# Sensor.net
KiCad netlist of a schematic drawn in Altium Designer
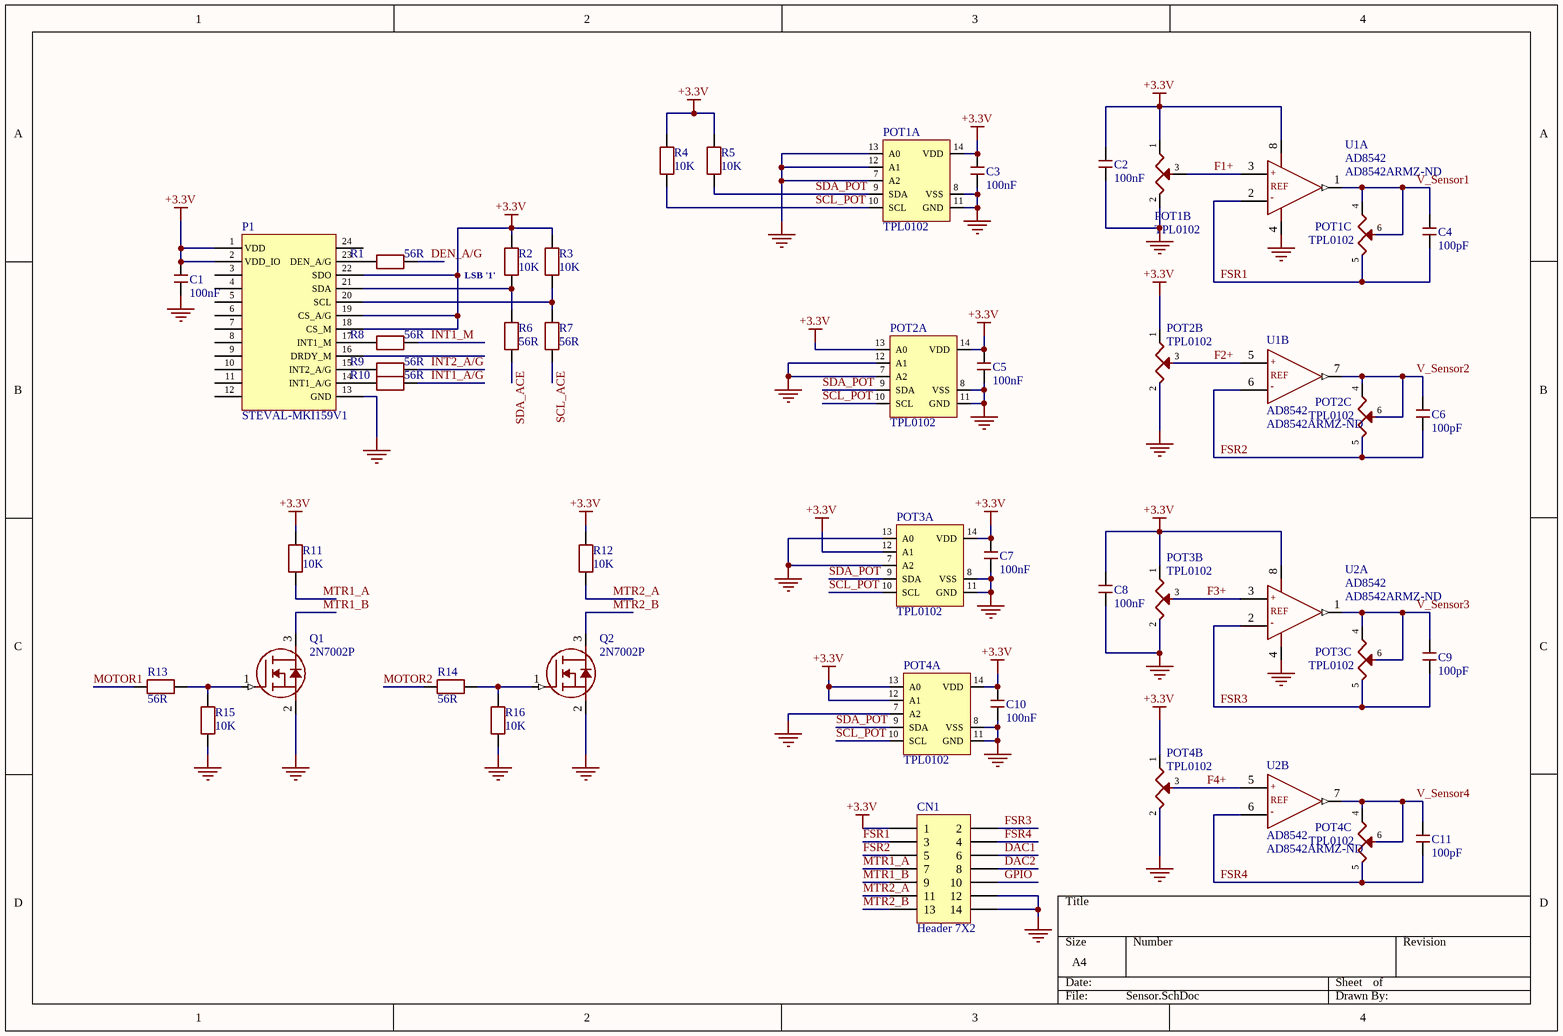
[diagram p0: Sensor.SchDoc]

(export (version "E")
  (design (tool "Eeschema 10.0.6"))
  (components
    (comp (ref "C1")
      (value "100nF")
      (footprint "CAP0805[2012]MD-BO")
      (description "CERAMIC SMD 0805 100nF 50V 10% X7R")
      (libsource (lib "Estimulador") (part "SMD 0805 100nF 50V 10% X7R"))
    )
    (comp (ref "C2")
      (value "100nF")
      (footprint "CAP0805[2012]MD-BO")
      (description "CERAMIC SMD 0805 100nF 50V 10% X7R")
      (libsource (lib "Estimulador") (part "SMD 0805 100nF 50V 10% X7R"))
    )
    (comp (ref "C3")
      (value "100nF")
      (footprint "CAP0805[2012]MD-BO")
      (description "CERAMIC SMD 0805 100nF 50V 10% X7R")
      (libsource (lib "Estimulador") (part "SMD 0805 100nF 50V 10% X7R"))
    )
    (comp (ref "C4")
      (value "100pF")
      (footprint "CAP0805[2012]MD-BO")
      (description "CERAMIC SMD 0805 100pF 50V 5% C0G")
      (libsource (lib "Estimulador") (part "SMD 0805 100pF 50V 5% C0G"))
    )
    (comp (ref "C5")
      (value "100nF")
      (footprint "CAP0805[2012]MD-BO")
      (description "CERAMIC SMD 0805 100nF 50V 10% X7R")
      (libsource (lib "Estimulador") (part "SMD 0805 100nF 50V 10% X7R"))
    )
    (comp (ref "C6")
      (value "100pF")
      (footprint "CAP0805[2012]MD-BO")
      (description "CERAMIC SMD 0805 100pF 50V 5% C0G")
      (libsource (lib "Estimulador") (part "SMD 0805 100pF 50V 5% C0G"))
    )
    (comp (ref "C7")
      (value "100nF")
      (footprint "CAP0805[2012]MD-BO")
      (description "CERAMIC SMD 0805 100nF 50V 10% X7R")
      (libsource (lib "Estimulador") (part "SMD 0805 100nF 50V 10% X7R"))
    )
    (comp (ref "C8")
      (value "100nF")
      (footprint "CAP0805[2012]MD-BO")
      (description "CERAMIC SMD 0805 100nF 50V 10% X7R")
      (libsource (lib "Estimulador") (part "SMD 0805 100nF 50V 10% X7R"))
    )
    (comp (ref "C9")
      (value "100pF")
      (footprint "CAP0805[2012]MD-BO")
      (description "CERAMIC SMD 0805 100pF 50V 5% C0G")
      (libsource (lib "Estimulador") (part "SMD 0805 100pF 50V 5% C0G"))
    )
    (comp (ref "C10")
      (value "100nF")
      (footprint "CAP0805[2012]MD-BO")
      (description "CERAMIC SMD 0805 100nF 50V 10% X7R")
      (libsource (lib "Estimulador") (part "SMD 0805 100nF 50V 10% X7R"))
    )
    (comp (ref "C11")
      (value "100pF")
      (footprint "CAP0805[2012]MD-BO")
      (description "CERAMIC SMD 0805 100pF 50V 5% C0G")
      (libsource (lib "Estimulador") (part "SMD 0805 100pF 50V 5% C0G"))
    )
    (comp (ref "CN1")
      (value "Header 7X2")
      (footprint "HDR2X7")
      (description "Header, 7-Pin, Dual row")
      (fields (field (name "PUBLISHER") "Altium Limited"))
      (libsource (lib "Miscellaneous Connectors") (part "Header 7X2"))
    )
    (comp (ref "P1")
      (value "STEVAL-MKI159V1")
      (footprint "STEVAL-MKI159V1 (2)")
      (description "STEVAL-MKI159V1 MEMS")
      (libsource (lib "MastersSystem") (part "STEVAL-MKI159V1"))
    )
    (comp (ref "POT1")
      (value "TPL0102")
      (footprint "TPL0102")
      (libsource (lib "MastersSystem2") (part "TPL0102"))
    )
    (comp (ref "POT2") (value "TPL0102") (footprint "TPL0102") (libsource (lib "") (part "TPL0102_1")))
    (comp (ref "POT3") (value "TPL0102") (footprint "TPL0102") (libsource (lib "") (part "TPL0102_1")))
    (comp (ref "POT4")
      (value "TPL0102")
      (footprint "TPL0102")
      (libsource (lib "MastersSystem2") (part "TPL0102"))
    )
    (comp (ref "Q1")
      (value "2N7002P")
      (footprint "SOT23-3")
      (description "MOSFET N-CH 60V 360mA SOT23-3")
      (libsource (lib "Transistors") (part "2N7002P,215"))
    )
    (comp (ref "Q2")
      (value "2N7002P")
      (footprint "SOT23-3")
      (description "MOSFET N-CH 60V 360mA SOT23-3")
      (libsource (lib "Transistors") (part "2N7002P,215"))
    )
    (comp (ref "R1")
      (value "56R")
      (footprint "RES0805[2012]MD-BO")
      (description "RESISTOR SMD 0805 56R 5% 0.125W")
      (libsource (lib "") (part "SMD 0805 56R 5% 0.125W_1"))
    )
    (comp (ref "R2")
      (value "10K")
      (footprint "RES0805[2012]MD")
      (description "RESISTOR SMD 0805 10K 5% 0.125W")
      (libsource (lib "Estimulador") (part "SMD 0805 10K 5% 0.125W"))
    )
    (comp (ref "R3")
      (value "10K")
      (footprint "RES0805[2012]MD")
      (description "RESISTOR SMD 0805 10K 5% 0.125W")
      (libsource (lib "Estimulador") (part "SMD 0805 10K 5% 0.125W"))
    )
    (comp (ref "R4")
      (value "10K")
      (footprint "RES0805[2012]MD")
      (description "RESISTOR SMD 0805 10K 5% 0.125W")
      (libsource (lib "Estimulador") (part "SMD 0805 10K 5% 0.125W"))
    )
    (comp (ref "R5")
      (value "10K")
      (footprint "RES0805[2012]MD")
      (description "RESISTOR SMD 0805 10K 5% 0.125W")
      (libsource (lib "Estimulador") (part "SMD 0805 10K 5% 0.125W"))
    )
    (comp (ref "R6")
      (value "56R")
      (footprint "RES0805[2012]MD-BO")
      (description "RESISTOR SMD 0805 56R 5% 0.125W")
      (libsource (lib "Resistors") (part "SMD 0805 56R 5% 0.125W"))
    )
    (comp (ref "R7")
      (value "56R")
      (footprint "RES0805[2012]MD-BO")
      (description "RESISTOR SMD 0805 56R 5% 0.125W")
      (libsource (lib "Resistors") (part "SMD 0805 56R 5% 0.125W"))
    )
    (comp (ref "R8")
      (value "56R")
      (footprint "RES0805[2012]MD-BO")
      (description "RESISTOR SMD 0805 56R 5% 0.125W")
      (libsource (lib "") (part "SMD 0805 56R 5% 0.125W_1"))
    )
    (comp (ref "R9")
      (value "56R")
      (footprint "RES0805[2012]MD-BO")
      (description "RESISTOR SMD 0805 56R 5% 0.125W")
      (libsource (lib "") (part "SMD 0805 56R 5% 0.125W_1"))
    )
    (comp (ref "R10")
      (value "56R")
      (footprint "RES0805[2012]MD-BO")
      (description "RESISTOR SMD 0805 56R 5% 0.125W")
      (libsource (lib "") (part "SMD 0805 56R 5% 0.125W_1"))
    )
    (comp (ref "R11")
      (value "10K")
      (footprint "RES0805[2012]MD-BO")
      (description "RESISTOR SMD 0805 10K 5% 0.125W")
      (libsource (lib "Estimulador") (part "SMD 0805 10K 5% 0.125W"))
    )
    (comp (ref "R12")
      (value "10K")
      (footprint "RES0805[2012]MD-BO")
      (description "RESISTOR SMD 0805 10K 5% 0.125W")
      (libsource (lib "Estimulador") (part "SMD 0805 10K 5% 0.125W"))
    )
    (comp (ref "R13")
      (value "56R")
      (footprint "RES0805[2012]MD-BO")
      (description "RESISTOR SMD 0805 56R 5% 0.125W")
      (libsource (lib "Estimulador") (part "SMD 0805 56R 5% 0.125W"))
    )
    (comp (ref "R14")
      (value "56R")
      (footprint "RES0805[2012]MD-BO")
      (description "RESISTOR SMD 0805 56R 5% 0.125W")
      (libsource (lib "Estimulador") (part "SMD 0805 56R 5% 0.125W"))
    )
    (comp (ref "R15")
      (value "10K")
      (footprint "RES0805[2012]MD-BO")
      (description "RESISTOR SMD 0805 10K 5% 0.125W")
      (libsource (lib "Estimulador") (part "SMD 0805 10K 5% 0.125W"))
    )
    (comp (ref "R16")
      (value "10K")
      (footprint "RES0805[2012]MD-BO")
      (description "RESISTOR SMD 0805 10K 5% 0.125W")
      (libsource (lib "Estimulador") (part "SMD 0805 10K 5% 0.125W"))
    )
    (comp (ref "U1")
      (value "AD8542")
      (footprint "MSOP8")
      (fields (field (name "SUPPLIER PART NUMBER 1") "AD8542ARMZ-ND"))
      (libsource (lib "MastersSystem") (part "AD8542"))
    )
    (comp (ref "U2")
      (value "AD8542")
      (footprint "MSOP8")
      (fields (field (name "SUPPLIER PART NUMBER 1") "AD8542ARMZ-ND"))
      (libsource (lib "MastersSystem") (part "AD8542"))
    )
  )
  (nets
    (net (code "1") (name "+3.3V") (class "Default")
      (node (ref "C1") (pin "1") (pinfunction "1_1") (pintype "passive"))
      (node (ref "C10") (pin "1") (pinfunction "1_1") (pintype "passive"))
      (node (ref "C2") (pin "1") (pinfunction "1_1") (pintype "passive"))
      (node (ref "C3") (pin "1") (pinfunction "1_1") (pintype "passive"))
      (node (ref "C5") (pin "1") (pinfunction "1_1") (pintype "passive"))
      (node (ref "C7") (pin "1") (pinfunction "1_1") (pintype "passive"))
      (node (ref "C8") (pin "1") (pinfunction "1_1") (pintype "passive"))
      (node (ref "CN1") (pin "1") (pinfunction "1_1") (pintype "passive"))
      (node (ref "P1") (pin "1") (pinfunction "VDD_1") (pintype "passive"))
      (node (ref "P1") (pin "18") (pinfunction "CS_M_18") (pintype "passive"))
      (node (ref "P1") (pin "19") (pinfunction "CS_A/G_19") (pintype "passive"))
      (node (ref "P1") (pin "2") (pinfunction "VDD_IO_2") (pintype "passive"))
      (node (ref "P1") (pin "22") (pinfunction "SDO_22") (pintype "passive"))
      (node (ref "POT1") (pin "1") (pinfunction "HA_1") (pintype "passive"))
      (node (ref "POT1") (pin "14") (pinfunction "VDD_14") (pintype "passive"))
      (node (ref "POT2") (pin "1") (pinfunction "HA_1") (pintype "passive"))
      (node (ref "POT2") (pin "13") (pinfunction "A0_13") (pintype "passive"))
      (node (ref "POT2") (pin "14") (pinfunction "VDD_14") (pintype "passive"))
      (node (ref "POT3") (pin "1") (pinfunction "HA_1") (pintype "passive"))
      (node (ref "POT3") (pin "12") (pinfunction "A1_12") (pintype "passive"))
      (node (ref "POT3") (pin "14") (pinfunction "VDD_14") (pintype "passive"))
      (node (ref "POT4") (pin "1") (pinfunction "HA_1") (pintype "passive"))
      (node (ref "POT4") (pin "12") (pinfunction "A1_12") (pintype "passive"))
      (node (ref "POT4") (pin "13") (pinfunction "A0_13") (pintype "passive"))
      (node (ref "POT4") (pin "14") (pinfunction "VDD_14") (pintype "passive"))
      (node (ref "R11") (pin "2") (pinfunction "2_2") (pintype "passive"))
      (node (ref "R12") (pin "2") (pinfunction "2_2") (pintype "passive"))
      (node (ref "R2") (pin "2") (pinfunction "2_2") (pintype "passive"))
      (node (ref "R3") (pin "2") (pinfunction "2_2") (pintype "passive"))
      (node (ref "R4") (pin "2") (pinfunction "2_2") (pintype "passive"))
      (node (ref "R5") (pin "2") (pinfunction "2_2") (pintype "passive"))
      (node (ref "U1") (pin "8") (pinfunction "V+_8") (pintype "power_in"))
      (node (ref "U2") (pin "8") (pinfunction "V+_8") (pintype "power_in"))
    )
    (net (code "2") (name "/DAC1") (class "Default")
      (node (ref "CN1") (pin "6") (pinfunction "6_6") (pintype "passive"))
    )
    (net (code "3") (name "/DAC2") (class "Default")
      (node (ref "CN1") (pin "8") (pinfunction "8_8") (pintype "passive"))
    )
    (net (code "4") (name "/DEN_A{slash}G") (class "Default")
      (node (ref "R1") (pin "1") (pinfunction "1_1") (pintype "passive"))
    )
    (net (code "5") (name "/F1+") (class "Default")
      (node (ref "POT1") (pin "3") (pinfunction "WA_3") (pintype "passive"))
      (node (ref "U1") (pin "3") (pinfunction "+IN_A_3") (pintype "passive"))
    )
    (net (code "6") (name "/F2+") (class "Default")
      (node (ref "POT2") (pin "3") (pinfunction "WA_3") (pintype "passive"))
      (node (ref "U1") (pin "5") (pinfunction "+IN_B_5") (pintype "passive"))
    )
    (net (code "7") (name "/F3+") (class "Default")
      (node (ref "POT3") (pin "3") (pinfunction "WA_3") (pintype "passive"))
      (node (ref "U2") (pin "3") (pinfunction "+IN_A_3") (pintype "passive"))
    )
    (net (code "8") (name "/F4+") (class "Default")
      (node (ref "POT4") (pin "3") (pinfunction "WA_3") (pintype "passive"))
      (node (ref "U2") (pin "5") (pinfunction "+IN_B_5") (pintype "passive"))
    )
    (net (code "9") (name "/FSR1") (class "Default")
      (node (ref "C4") (pin "2") (pinfunction "2_2") (pintype "passive"))
      (node (ref "CN1") (pin "3") (pinfunction "3_3") (pintype "passive"))
      (node (ref "POT1") (pin "5") (pinfunction "LB_5") (pintype "passive"))
      (node (ref "U1") (pin "2") (pinfunction "-IN_A_2") (pintype "passive"))
    )
    (net (code "10") (name "/FSR2") (class "Default")
      (node (ref "C6") (pin "2") (pinfunction "2_2") (pintype "passive"))
      (node (ref "CN1") (pin "5") (pinfunction "5_5") (pintype "passive"))
      (node (ref "POT2") (pin "5") (pinfunction "LB_5") (pintype "passive"))
      (node (ref "U1") (pin "6") (pinfunction "-IN_B_6") (pintype "passive"))
    )
    (net (code "11") (name "/FSR3") (class "Default")
      (node (ref "C9") (pin "2") (pinfunction "2_2") (pintype "passive"))
      (node (ref "CN1") (pin "2") (pinfunction "2_2") (pintype "passive"))
      (node (ref "POT3") (pin "5") (pinfunction "LB_5") (pintype "passive"))
      (node (ref "U2") (pin "2") (pinfunction "-IN_A_2") (pintype "passive"))
    )
    (net (code "12") (name "/FSR4") (class "Default")
      (node (ref "C11") (pin "2") (pinfunction "2_2") (pintype "passive"))
      (node (ref "CN1") (pin "4") (pinfunction "4_4") (pintype "passive"))
      (node (ref "POT4") (pin "5") (pinfunction "LB_5") (pintype "passive"))
      (node (ref "U2") (pin "6") (pinfunction "-IN_B_6") (pintype "passive"))
    )
    (net (code "13") (name "/GPIO") (class "Default")
      (node (ref "CN1") (pin "10") (pinfunction "10_10") (pintype "passive"))
    )
    (net (code "14") (name "/INT1_A{slash}G") (class "Default")
      (node (ref "R10") (pin "1") (pinfunction "1_1") (pintype "passive"))
    )
    (net (code "15") (name "/INT1_M") (class "Default")
      (node (ref "R8") (pin "1") (pinfunction "1_1") (pintype "passive"))
    )
    (net (code "16") (name "/INT2_A{slash}G") (class "Default")
      (node (ref "R9") (pin "1") (pinfunction "1_1") (pintype "passive"))
    )
    (net (code "17") (name "/MOTOR1") (class "Default")
      (node (ref "R13") (pin "1") (pinfunction "1_1") (pintype "passive"))
    )
    (net (code "18") (name "/MOTOR2") (class "Default")
      (node (ref "R14") (pin "1") (pinfunction "1_1") (pintype "passive"))
    )
    (net (code "19") (name "/MTR1_A") (class "Default")
      (node (ref "CN1") (pin "7") (pinfunction "7_7") (pintype "passive"))
      (node (ref "R11") (pin "1") (pinfunction "1_1") (pintype "passive"))
    )
    (net (code "20") (name "/MTR1_B") (class "Default")
      (node (ref "CN1") (pin "9") (pinfunction "9_9") (pintype "passive"))
      (node (ref "Q1") (pin "3") (pinfunction "DRAIN_3") (pintype "passive"))
    )
    (net (code "21") (name "/MTR2_A") (class "Default")
      (node (ref "CN1") (pin "11") (pinfunction "11_11") (pintype "passive"))
      (node (ref "R12") (pin "1") (pinfunction "1_1") (pintype "passive"))
    )
    (net (code "22") (name "/MTR2_B") (class "Default")
      (node (ref "CN1") (pin "13") (pinfunction "13_13") (pintype "passive"))
      (node (ref "Q2") (pin "3") (pinfunction "DRAIN_3") (pintype "passive"))
    )
    (net (code "23") (name "/SCL_ACE") (class "Default")
      (node (ref "R7") (pin "2") (pinfunction "2_2") (pintype "passive"))
    )
    (net (code "24") (name "/SCL_POT") (class "Default")
      (node (ref "POT1") (pin "10") (pinfunction "SCL_10") (pintype "passive"))
      (node (ref "POT2") (pin "10") (pinfunction "SCL_10") (pintype "passive"))
      (node (ref "POT3") (pin "10") (pinfunction "SCL_10") (pintype "passive"))
      (node (ref "POT4") (pin "10") (pinfunction "SCL_10") (pintype "passive"))
      (node (ref "R4") (pin "1") (pinfunction "1_1") (pintype "passive"))
    )
    (net (code "25") (name "/SDA_ACE") (class "Default")
      (node (ref "R6") (pin "2") (pinfunction "2_2") (pintype "passive"))
    )
    (net (code "26") (name "/SDA_POT") (class "Default")
      (node (ref "POT1") (pin "9") (pinfunction "SDA_9") (pintype "passive"))
      (node (ref "POT2") (pin "9") (pinfunction "SDA_9") (pintype "passive"))
      (node (ref "POT3") (pin "9") (pinfunction "SDA_9") (pintype "passive"))
      (node (ref "POT4") (pin "9") (pinfunction "SDA_9") (pintype "passive"))
      (node (ref "R5") (pin "1") (pinfunction "1_1") (pintype "passive"))
    )
    (net (code "27") (name "/V_Sensor1") (class "Default")
      (node (ref "C4") (pin "1") (pinfunction "1_1") (pintype "passive"))
      (node (ref "POT1") (pin "4") (pinfunction "HB_4") (pintype "passive"))
      (node (ref "POT1") (pin "6") (pinfunction "WB_6") (pintype "passive"))
      (node (ref "U1") (pin "1") (pinfunction "OUT_A_1") (pintype "output"))
    )
    (net (code "28") (name "/V_Sensor2") (class "Default")
      (node (ref "C6") (pin "1") (pinfunction "1_1") (pintype "passive"))
      (node (ref "POT2") (pin "4") (pinfunction "HB_4") (pintype "passive"))
      (node (ref "POT2") (pin "6") (pinfunction "WB_6") (pintype "passive"))
      (node (ref "U1") (pin "7") (pinfunction "OUT_B_7") (pintype "output"))
    )
    (net (code "29") (name "/V_Sensor3") (class "Default")
      (node (ref "C9") (pin "1") (pinfunction "1_1") (pintype "passive"))
      (node (ref "POT3") (pin "4") (pinfunction "HB_4") (pintype "passive"))
      (node (ref "POT3") (pin "6") (pinfunction "WB_6") (pintype "passive"))
      (node (ref "U2") (pin "1") (pinfunction "OUT_A_1") (pintype "output"))
    )
    (net (code "30") (name "/V_Sensor4") (class "Default")
      (node (ref "C11") (pin "1") (pinfunction "1_1") (pintype "passive"))
      (node (ref "POT4") (pin "4") (pinfunction "HB_4") (pintype "passive"))
      (node (ref "POT4") (pin "6") (pinfunction "WB_6") (pintype "passive"))
      (node (ref "U2") (pin "7") (pinfunction "OUT_B_7") (pintype "output"))
    )
    (net (code "31") (name "GND") (class "Default")
      (node (ref "C1") (pin "2") (pinfunction "2_2") (pintype "passive"))
      (node (ref "C10") (pin "2") (pinfunction "2_2") (pintype "passive"))
      (node (ref "C2") (pin "2") (pinfunction "2_2") (pintype "passive"))
      (node (ref "C3") (pin "2") (pinfunction "2_2") (pintype "passive"))
      (node (ref "C5") (pin "2") (pinfunction "2_2") (pintype "passive"))
      (node (ref "C7") (pin "2") (pinfunction "2_2") (pintype "passive"))
      (node (ref "C8") (pin "2") (pinfunction "2_2") (pintype "passive"))
      (node (ref "CN1") (pin "12") (pinfunction "12_12") (pintype "passive"))
      (node (ref "CN1") (pin "14") (pinfunction "14_14") (pintype "passive"))
      (node (ref "P1") (pin "13") (pinfunction "GND_13") (pintype "passive"))
      (node (ref "POT1") (pin "11") (pinfunction "GND_11") (pintype "passive"))
      (node (ref "POT1") (pin "12") (pinfunction "A1_12") (pintype "passive"))
      (node (ref "POT1") (pin "13") (pinfunction "A0_13") (pintype "passive"))
      (node (ref "POT1") (pin "2") (pinfunction "LA_2") (pintype "passive"))
      (node (ref "POT1") (pin "7") (pinfunction "A2_7") (pintype "passive"))
      (node (ref "POT1") (pin "8") (pinfunction "VSS_8") (pintype "passive"))
      (node (ref "POT2") (pin "11") (pinfunction "GND_11") (pintype "passive"))
      (node (ref "POT2") (pin "12") (pinfunction "A1_12") (pintype "passive"))
      (node (ref "POT2") (pin "2") (pinfunction "LA_2") (pintype "passive"))
      (node (ref "POT2") (pin "7") (pinfunction "A2_7") (pintype "passive"))
      (node (ref "POT2") (pin "8") (pinfunction "VSS_8") (pintype "passive"))
      (node (ref "POT3") (pin "11") (pinfunction "GND_11") (pintype "passive"))
      (node (ref "POT3") (pin "13") (pinfunction "A0_13") (pintype "passive"))
      (node (ref "POT3") (pin "2") (pinfunction "LA_2") (pintype "passive"))
      (node (ref "POT3") (pin "7") (pinfunction "A2_7") (pintype "passive"))
      (node (ref "POT3") (pin "8") (pinfunction "VSS_8") (pintype "passive"))
      (node (ref "POT4") (pin "11") (pinfunction "GND_11") (pintype "passive"))
      (node (ref "POT4") (pin "2") (pinfunction "LA_2") (pintype "passive"))
      (node (ref "POT4") (pin "7") (pinfunction "A2_7") (pintype "passive"))
      (node (ref "POT4") (pin "8") (pinfunction "VSS_8") (pintype "passive"))
      (node (ref "Q1") (pin "2") (pinfunction "SOURCE_2") (pintype "passive"))
      (node (ref "Q2") (pin "2") (pinfunction "SOURCE_2") (pintype "passive"))
      (node (ref "R15") (pin "1") (pinfunction "1_1") (pintype "passive"))
      (node (ref "R16") (pin "1") (pinfunction "1_1") (pintype "passive"))
      (node (ref "U1") (pin "4") (pinfunction "V-_4") (pintype "power_in"))
      (node (ref "U2") (pin "4") (pinfunction "V-_4") (pintype "power_in"))
    )
    (net (code "32") (name "Net-(P1-DEN_A{slash}G)") (class "Default")
      (node (ref "P1") (pin "23") (pinfunction "DEN_A/G_23") (pintype "passive"))
      (node (ref "R1") (pin "2") (pinfunction "2_2") (pintype "passive"))
    )
    (net (code "33") (name "Net-(P1-INT1_A{slash}G)") (class "Default")
      (node (ref "P1") (pin "14") (pinfunction "INT1_A/G_14") (pintype "passive"))
      (node (ref "R10") (pin "2") (pinfunction "2_2") (pintype "passive"))
    )
    (net (code "34") (name "Net-(P1-INT1_M)") (class "Default")
      (node (ref "P1") (pin "17") (pinfunction "INT1_M_17") (pintype "passive"))
      (node (ref "R8") (pin "2") (pinfunction "2_2") (pintype "passive"))
    )
    (net (code "35") (name "Net-(P1-INT2_A{slash}G)") (class "Default")
      (node (ref "P1") (pin "15") (pinfunction "INT2_A/G_15") (pintype "passive"))
      (node (ref "R9") (pin "2") (pinfunction "2_2") (pintype "passive"))
    )
    (net (code "36") (name "Net-(P1-SCL)") (class "Default")
      (node (ref "P1") (pin "20") (pinfunction "SCL_20") (pintype "passive"))
      (node (ref "R3") (pin "1") (pinfunction "1_1") (pintype "passive"))
      (node (ref "R7") (pin "1") (pinfunction "1_1") (pintype "passive"))
    )
    (net (code "37") (name "Net-(P1-SDA)") (class "Default")
      (node (ref "P1") (pin "21") (pinfunction "SDA_21") (pintype "passive"))
      (node (ref "R2") (pin "1") (pinfunction "1_1") (pintype "passive"))
      (node (ref "R6") (pin "1") (pinfunction "1_1") (pintype "passive"))
    )
    (net (code "38") (name "Net-(Q1-GATE)") (class "Default")
      (node (ref "Q1") (pin "1") (pinfunction "GATE_1") (pintype "input"))
      (node (ref "R13") (pin "2") (pinfunction "2_2") (pintype "passive"))
      (node (ref "R15") (pin "2") (pinfunction "2_2") (pintype "passive"))
    )
    (net (code "39") (name "Net-(Q2-GATE)") (class "Default")
      (node (ref "Q2") (pin "1") (pinfunction "GATE_1") (pintype "input"))
      (node (ref "R14") (pin "2") (pinfunction "2_2") (pintype "passive"))
      (node (ref "R16") (pin "2") (pinfunction "2_2") (pintype "passive"))
    )
    (net (code "40") (name "unconnected-(P1-DRDY_M-Pad16)") (class "Default")
      (node (ref "P1") (pin "16") (pinfunction "DRDY_M_16") (pintype "passive"))
    )
    (net (code "41") (name "unconnected-(P1-NC-Pad3)") (class "Default")
      (node (ref "P1") (pin "3") (pinfunction "NC_3") (pintype "passive"))
    )
    (net (code "42") (name "unconnected-(P1-NC-Pad4)") (class "Default")
      (node (ref "P1") (pin "4") (pinfunction "NC_4") (pintype "passive"))
    )
    (net (code "43") (name "unconnected-(P1-NC-Pad5)") (class "Default")
      (node (ref "P1") (pin "5") (pinfunction "NC_5") (pintype "passive"))
    )
    (net (code "44") (name "unconnected-(P1-NC-Pad6)") (class "Default")
      (node (ref "P1") (pin "6") (pinfunction "NC_6") (pintype "passive"))
    )
    (net (code "45") (name "unconnected-(P1-NC-Pad7)") (class "Default")
      (node (ref "P1") (pin "7") (pinfunction "NC_7") (pintype "passive"))
    )
    (net (code "46") (name "unconnected-(P1-NC-Pad8)") (class "Default")
      (node (ref "P1") (pin "8") (pinfunction "NC_8") (pintype "passive"))
    )
    (net (code "47") (name "unconnected-(P1-NC-Pad9)") (class "Default")
      (node (ref "P1") (pin "9") (pinfunction "NC_9") (pintype "passive"))
    )
    (net (code "48") (name "unconnected-(P1-NC-Pad10)") (class "Default")
      (node (ref "P1") (pin "10") (pinfunction "NC_10") (pintype "passive"))
    )
    (net (code "49") (name "unconnected-(P1-NC-Pad11)") (class "Default")
      (node (ref "P1") (pin "11") (pinfunction "NC_11") (pintype "passive"))
    )
    (net (code "50") (name "unconnected-(P1-NC-Pad12)") (class "Default")
      (node (ref "P1") (pin "12") (pinfunction "NC_12") (pintype "passive"))
    )
    (net (code "51") (name "unconnected-(P1-NC-Pad24)") (class "Default")
      (node (ref "P1") (pin "24") (pinfunction "NC_24") (pintype "passive"))
    )
  )
)
